# control_board.net
KiCad netlist of a schematic drawn in EasyEDA
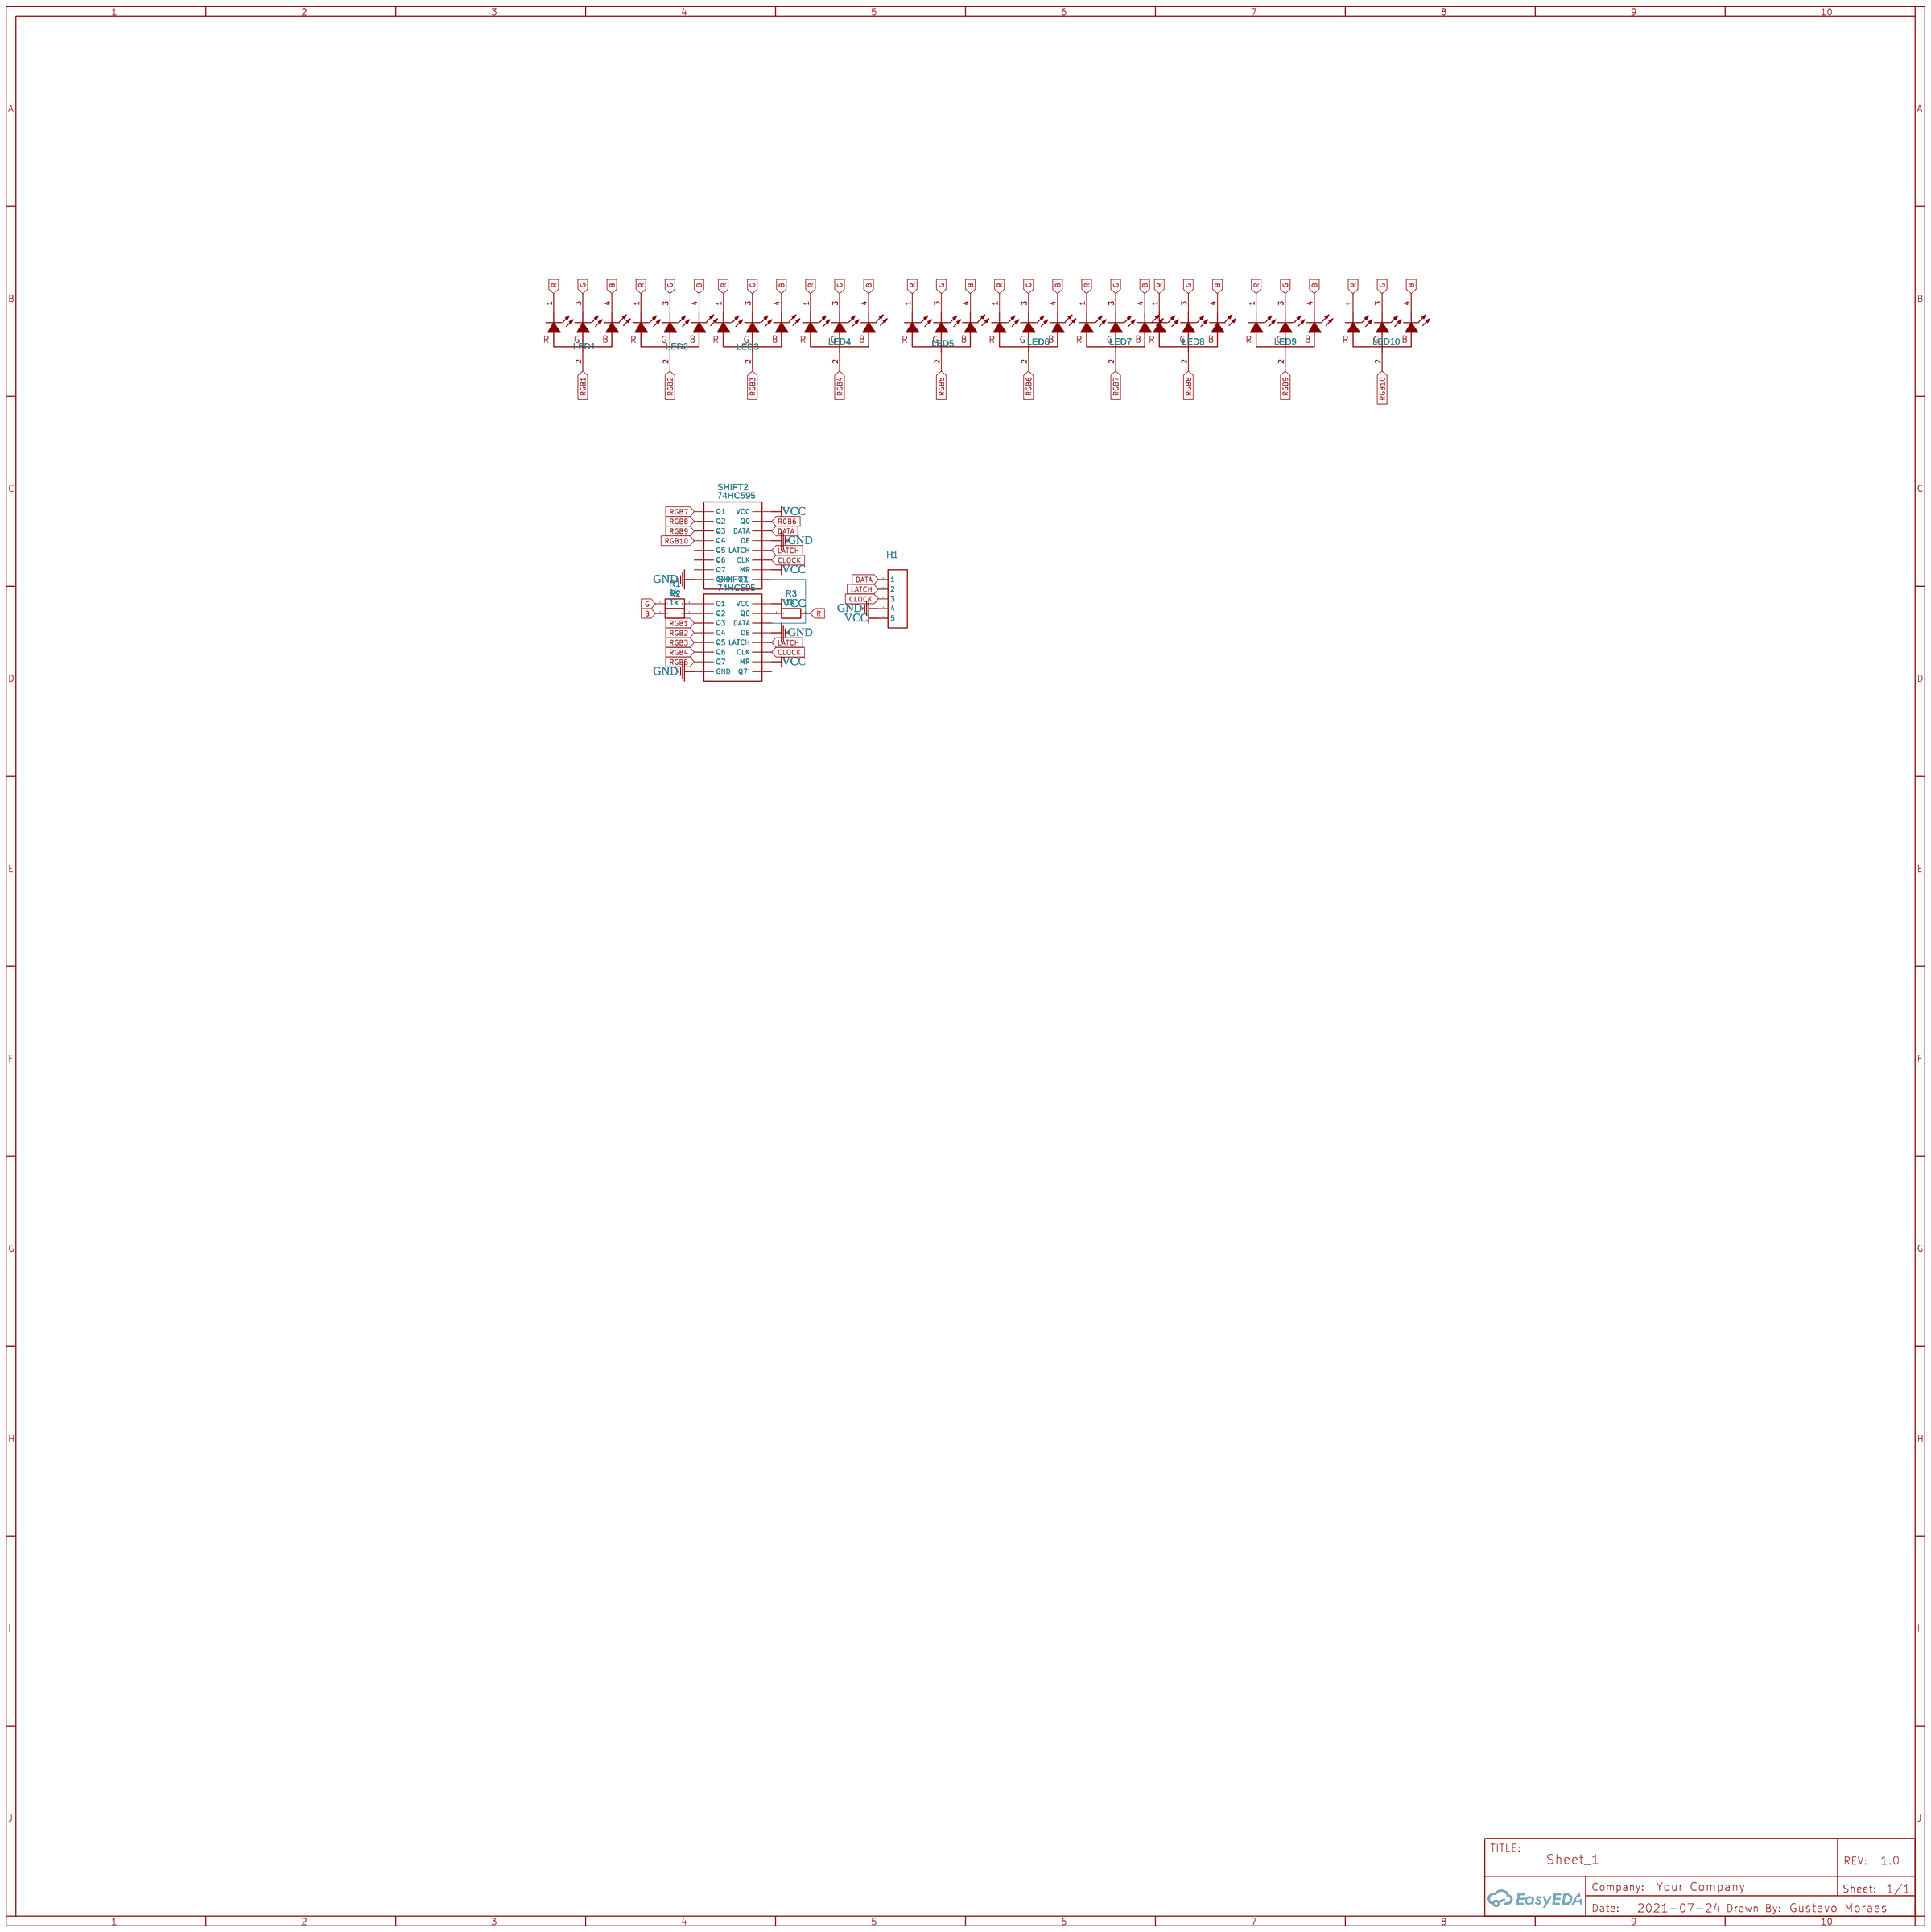
[diagram p0: schematic sheet]

(export (version "E")
  (design (tool "Eeschema 10.0.6"))
  (components
    (comp (ref "H1")
      (value "HDR-F-2.54_1x5")
      (fields (field (name "BOM_Supplier Part") "C50950"))
      (libsource (lib "") (part "HDR-F-2.54_1x5"))
    )
    (comp (ref "LED1")
      (value "φ5 RGB Transparent")
      (fields
        (field (name "BOM_Manufacturer Part") "φ5 RGB Transparent LED")
        (field (name "BOM_Supplier Part") "C32985")
      )
      (libsource (lib "") (part "φ5 RGB Transparent"))
    )
    (comp (ref "LED2")
      (value "φ5 RGB Transparent")
      (fields
        (field (name "BOM_Manufacturer Part") "φ5 RGB Transparent LED")
        (field (name "BOM_Supplier Part") "C32985")
      )
      (libsource (lib "") (part "φ5 RGB Transparent"))
    )
    (comp (ref "LED3")
      (value "φ5 RGB Transparent")
      (fields
        (field (name "BOM_Manufacturer Part") "φ5 RGB Transparent LED")
        (field (name "BOM_Supplier Part") "C32985")
      )
      (libsource (lib "") (part "φ5 RGB Transparent"))
    )
    (comp (ref "LED4")
      (value "φ5 RGB Transparent")
      (fields
        (field (name "BOM_Manufacturer Part") "φ5 RGB Transparent LED")
        (field (name "BOM_Supplier Part") "C32985")
      )
      (libsource (lib "") (part "φ5 RGB Transparent_1"))
    )
    (comp (ref "LED5")
      (value "φ5 RGB Transparent")
      (fields
        (field (name "BOM_Manufacturer Part") "φ5 RGB Transparent LED")
        (field (name "BOM_Supplier Part") "C32985")
      )
      (libsource (lib "") (part "φ5 RGB Transparent"))
    )
    (comp (ref "LED6")
      (value "φ5 RGB Transparent")
      (fields
        (field (name "BOM_Manufacturer Part") "φ5 RGB Transparent LED")
        (field (name "BOM_Supplier Part") "C32985")
      )
      (libsource (lib "") (part "φ5 RGB Transparent"))
    )
    (comp (ref "LED7")
      (value "φ5 RGB Transparent")
      (fields
        (field (name "BOM_Manufacturer Part") "φ5 RGB Transparent LED")
        (field (name "BOM_Supplier Part") "C32985")
      )
      (libsource (lib "") (part "φ5 RGB Transparent"))
    )
    (comp (ref "LED8")
      (value "φ5 RGB Transparent")
      (fields
        (field (name "BOM_Manufacturer Part") "φ5 RGB Transparent LED")
        (field (name "BOM_Supplier Part") "C32985")
      )
      (libsource (lib "") (part "φ5 RGB Transparent"))
    )
    (comp (ref "LED9")
      (value "φ5 RGB Transparent")
      (fields
        (field (name "BOM_Manufacturer Part") "φ5 RGB Transparent LED")
        (field (name "BOM_Supplier Part") "C32985")
      )
      (libsource (lib "") (part "φ5 RGB Transparent"))
    )
    (comp (ref "LED10")
      (value "φ5 RGB Transparent")
      (fields
        (field (name "BOM_Manufacturer Part") "φ5 RGB Transparent LED")
        (field (name "BOM_Supplier Part") "C32985")
      )
      (libsource (lib "") (part "φ5 RGB Transparent"))
    )
    (comp (ref "R1") (value "1k") (libsource (lib "") (part "R_AXIAL-0.3_EU")))
    (comp (ref "R2") (value "1k") (libsource (lib "") (part "R_AXIAL-0.3_EU")))
    (comp (ref "R3") (value "1k") (libsource (lib "") (part "R_AXIAL-0.3_EU")))
    (comp (ref "SHIFT1") (value "74HC595") (libsource (lib "") (part "74HC595")))
    (comp (ref "SHIFT2") (value "74HC595") (libsource (lib "") (part "74HC595")))
  )
  (nets
    (net (code "1") (name "B") (class "Default")
      (node (ref "LED1") (pin "4") (pinfunction "KB_4") (pintype "unspecified"))
      (node (ref "LED10") (pin "4") (pinfunction "KB_4") (pintype "unspecified"))
      (node (ref "LED2") (pin "4") (pinfunction "KB_4") (pintype "unspecified"))
      (node (ref "LED3") (pin "4") (pinfunction "KB_4") (pintype "unspecified"))
      (node (ref "LED4") (pin "4") (pinfunction "KB_4") (pintype "unspecified"))
      (node (ref "LED5") (pin "4") (pinfunction "KB_4") (pintype "unspecified"))
      (node (ref "LED6") (pin "4") (pinfunction "KB_4") (pintype "unspecified"))
      (node (ref "LED7") (pin "4") (pinfunction "KB_4") (pintype "unspecified"))
      (node (ref "LED8") (pin "4") (pinfunction "KB_4") (pintype "unspecified"))
      (node (ref "LED9") (pin "4") (pinfunction "KB_4") (pintype "unspecified"))
      (node (ref "R2") (pin "1") (pinfunction "1_1") (pintype "unspecified"))
    )
    (net (code "2") (name "CLOCK") (class "Default")
      (node (ref "H1") (pin "3") (pinfunction "3_3") (pintype "unspecified"))
      (node (ref "SHIFT1") (pin "11") (pinfunction "CLK_11") (pintype "unspecified"))
      (node (ref "SHIFT2") (pin "11") (pinfunction "CLK_11") (pintype "unspecified"))
    )
    (net (code "3") (name "DATA") (class "Default")
      (node (ref "H1") (pin "1") (pinfunction "1_1") (pintype "unspecified"))
      (node (ref "SHIFT2") (pin "14") (pinfunction "DATA_14") (pintype "unspecified"))
    )
    (net (code "4") (name "G") (class "Default")
      (node (ref "LED1") (pin "3") (pinfunction "KG_3") (pintype "unspecified"))
      (node (ref "LED10") (pin "3") (pinfunction "KG_3") (pintype "unspecified"))
      (node (ref "LED2") (pin "3") (pinfunction "KG_3") (pintype "unspecified"))
      (node (ref "LED3") (pin "3") (pinfunction "KG_3") (pintype "unspecified"))
      (node (ref "LED4") (pin "3") (pinfunction "KG_3") (pintype "unspecified"))
      (node (ref "LED5") (pin "3") (pinfunction "KG_3") (pintype "unspecified"))
      (node (ref "LED6") (pin "3") (pinfunction "KG_3") (pintype "unspecified"))
      (node (ref "LED7") (pin "3") (pinfunction "KG_3") (pintype "unspecified"))
      (node (ref "LED8") (pin "3") (pinfunction "KG_3") (pintype "unspecified"))
      (node (ref "LED9") (pin "3") (pinfunction "KG_3") (pintype "unspecified"))
      (node (ref "R1") (pin "1") (pinfunction "1_1") (pintype "unspecified"))
    )
    (net (code "5") (name "GND") (class "Default")
      (node (ref "H1") (pin "4") (pinfunction "4_4") (pintype "unspecified"))
      (node (ref "SHIFT1") (pin "13") (pinfunction "OE_13") (pintype "unspecified"))
      (node (ref "SHIFT1") (pin "8") (pinfunction "GND_8") (pintype "unspecified"))
      (node (ref "SHIFT2") (pin "13") (pinfunction "OE_13") (pintype "unspecified"))
      (node (ref "SHIFT2") (pin "8") (pinfunction "GND_8") (pintype "unspecified"))
    )
    (net (code "6") (name "LATCH") (class "Default")
      (node (ref "H1") (pin "2") (pinfunction "2_2") (pintype "unspecified"))
      (node (ref "SHIFT1") (pin "12") (pinfunction "LATCH_12") (pintype "unspecified"))
      (node (ref "SHIFT2") (pin "12") (pinfunction "LATCH_12") (pintype "unspecified"))
    )
    (net (code "7") (name "Net-(SHIFT1-DATA)") (class "Default")
      (node (ref "SHIFT1") (pin "14") (pinfunction "DATA_14") (pintype "unspecified"))
      (node (ref "SHIFT2") (pin "9") (pinfunction "Q7'_9") (pintype "unspecified"))
    )
    (net (code "8") (name "Net-(SHIFT1-Q0)") (class "Default")
      (node (ref "R3") (pin "1") (pinfunction "1_1") (pintype "unspecified"))
      (node (ref "SHIFT1") (pin "15") (pinfunction "Q0_15") (pintype "unspecified"))
    )
    (net (code "9") (name "Net-(SHIFT1-Q1)") (class "Default")
      (node (ref "R1") (pin "2") (pinfunction "2_2") (pintype "unspecified"))
      (node (ref "SHIFT1") (pin "1") (pinfunction "Q1_1") (pintype "unspecified"))
    )
    (net (code "10") (name "Net-(SHIFT1-Q2)") (class "Default")
      (node (ref "R2") (pin "2") (pinfunction "2_2") (pintype "unspecified"))
      (node (ref "SHIFT1") (pin "2") (pinfunction "Q2_2") (pintype "unspecified"))
    )
    (net (code "11") (name "R") (class "Default")
      (node (ref "LED1") (pin "1") (pinfunction "KR_1") (pintype "unspecified"))
      (node (ref "LED10") (pin "1") (pinfunction "KR_1") (pintype "unspecified"))
      (node (ref "LED2") (pin "1") (pinfunction "KR_1") (pintype "unspecified"))
      (node (ref "LED3") (pin "1") (pinfunction "KR_1") (pintype "unspecified"))
      (node (ref "LED4") (pin "1") (pinfunction "KR_1") (pintype "unspecified"))
      (node (ref "LED5") (pin "1") (pinfunction "KR_1") (pintype "unspecified"))
      (node (ref "LED6") (pin "1") (pinfunction "KR_1") (pintype "unspecified"))
      (node (ref "LED7") (pin "1") (pinfunction "KR_1") (pintype "unspecified"))
      (node (ref "LED8") (pin "1") (pinfunction "KR_1") (pintype "unspecified"))
      (node (ref "LED9") (pin "1") (pinfunction "KR_1") (pintype "unspecified"))
      (node (ref "R3") (pin "2") (pinfunction "2_2") (pintype "unspecified"))
    )
    (net (code "12") (name "RGB1") (class "Default")
      (node (ref "LED1") (pin "2") (pinfunction "CA_2") (pintype "unspecified"))
      (node (ref "SHIFT1") (pin "3") (pinfunction "Q3_3") (pintype "unspecified"))
    )
    (net (code "13") (name "RGB2") (class "Default")
      (node (ref "LED2") (pin "2") (pinfunction "CA_2") (pintype "unspecified"))
      (node (ref "SHIFT1") (pin "4") (pinfunction "Q4_4") (pintype "unspecified"))
    )
    (net (code "14") (name "RGB3") (class "Default")
      (node (ref "LED3") (pin "2") (pinfunction "CA_2") (pintype "unspecified"))
      (node (ref "SHIFT1") (pin "5") (pinfunction "Q5_5") (pintype "unspecified"))
    )
    (net (code "15") (name "RGB4") (class "Default")
      (node (ref "LED4") (pin "2") (pinfunction "CA_2") (pintype "unspecified"))
      (node (ref "SHIFT1") (pin "6") (pinfunction "Q6_6") (pintype "unspecified"))
    )
    (net (code "16") (name "RGB5") (class "Default")
      (node (ref "LED5") (pin "2") (pinfunction "CA_2") (pintype "unspecified"))
      (node (ref "SHIFT1") (pin "7") (pinfunction "Q7_7") (pintype "unspecified"))
    )
    (net (code "17") (name "RGB6") (class "Default")
      (node (ref "LED6") (pin "2") (pinfunction "CA_2") (pintype "unspecified"))
      (node (ref "SHIFT2") (pin "15") (pinfunction "Q0_15") (pintype "unspecified"))
    )
    (net (code "18") (name "RGB7") (class "Default")
      (node (ref "LED7") (pin "2") (pinfunction "CA_2") (pintype "unspecified"))
      (node (ref "SHIFT2") (pin "1") (pinfunction "Q1_1") (pintype "unspecified"))
    )
    (net (code "19") (name "RGB8") (class "Default")
      (node (ref "LED8") (pin "2") (pinfunction "CA_2") (pintype "unspecified"))
      (node (ref "SHIFT2") (pin "2") (pinfunction "Q2_2") (pintype "unspecified"))
    )
    (net (code "20") (name "RGB9") (class "Default")
      (node (ref "LED9") (pin "2") (pinfunction "CA_2") (pintype "unspecified"))
      (node (ref "SHIFT2") (pin "3") (pinfunction "Q3_3") (pintype "unspecified"))
    )
    (net (code "21") (name "RGB10") (class "Default")
      (node (ref "LED10") (pin "2") (pinfunction "CA_2") (pintype "unspecified"))
      (node (ref "SHIFT2") (pin "4") (pinfunction "Q4_4") (pintype "unspecified"))
    )
    (net (code "22") (name "VCC") (class "Default")
      (node (ref "H1") (pin "5") (pinfunction "5_5") (pintype "unspecified"))
      (node (ref "SHIFT1") (pin "10") (pinfunction "MR_10") (pintype "unspecified"))
      (node (ref "SHIFT1") (pin "16") (pinfunction "VCC_16") (pintype "unspecified"))
      (node (ref "SHIFT2") (pin "10") (pinfunction "MR_10") (pintype "unspecified"))
      (node (ref "SHIFT2") (pin "16") (pinfunction "VCC_16") (pintype "unspecified"))
    )
    (net (code "23") (name "unconnected-(SHIFT1-Q7'-Pad9)") (class "Default")
      (node (ref "SHIFT1") (pin "9") (pinfunction "Q7'_9") (pintype "unspecified"))
    )
    (net (code "24") (name "unconnected-(SHIFT2-Q5-Pad5)") (class "Default")
      (node (ref "SHIFT2") (pin "5") (pinfunction "Q5_5") (pintype "unspecified"))
    )
    (net (code "25") (name "unconnected-(SHIFT2-Q6-Pad6)") (class "Default")
      (node (ref "SHIFT2") (pin "6") (pinfunction "Q6_6") (pintype "unspecified"))
    )
    (net (code "26") (name "unconnected-(SHIFT2-Q7-Pad7)") (class "Default")
      (node (ref "SHIFT2") (pin "7") (pinfunction "Q7_7") (pintype "unspecified"))
    )
  )
)
